# interceptor.net
KiCad netlist of a schematic drawn in EAGLE
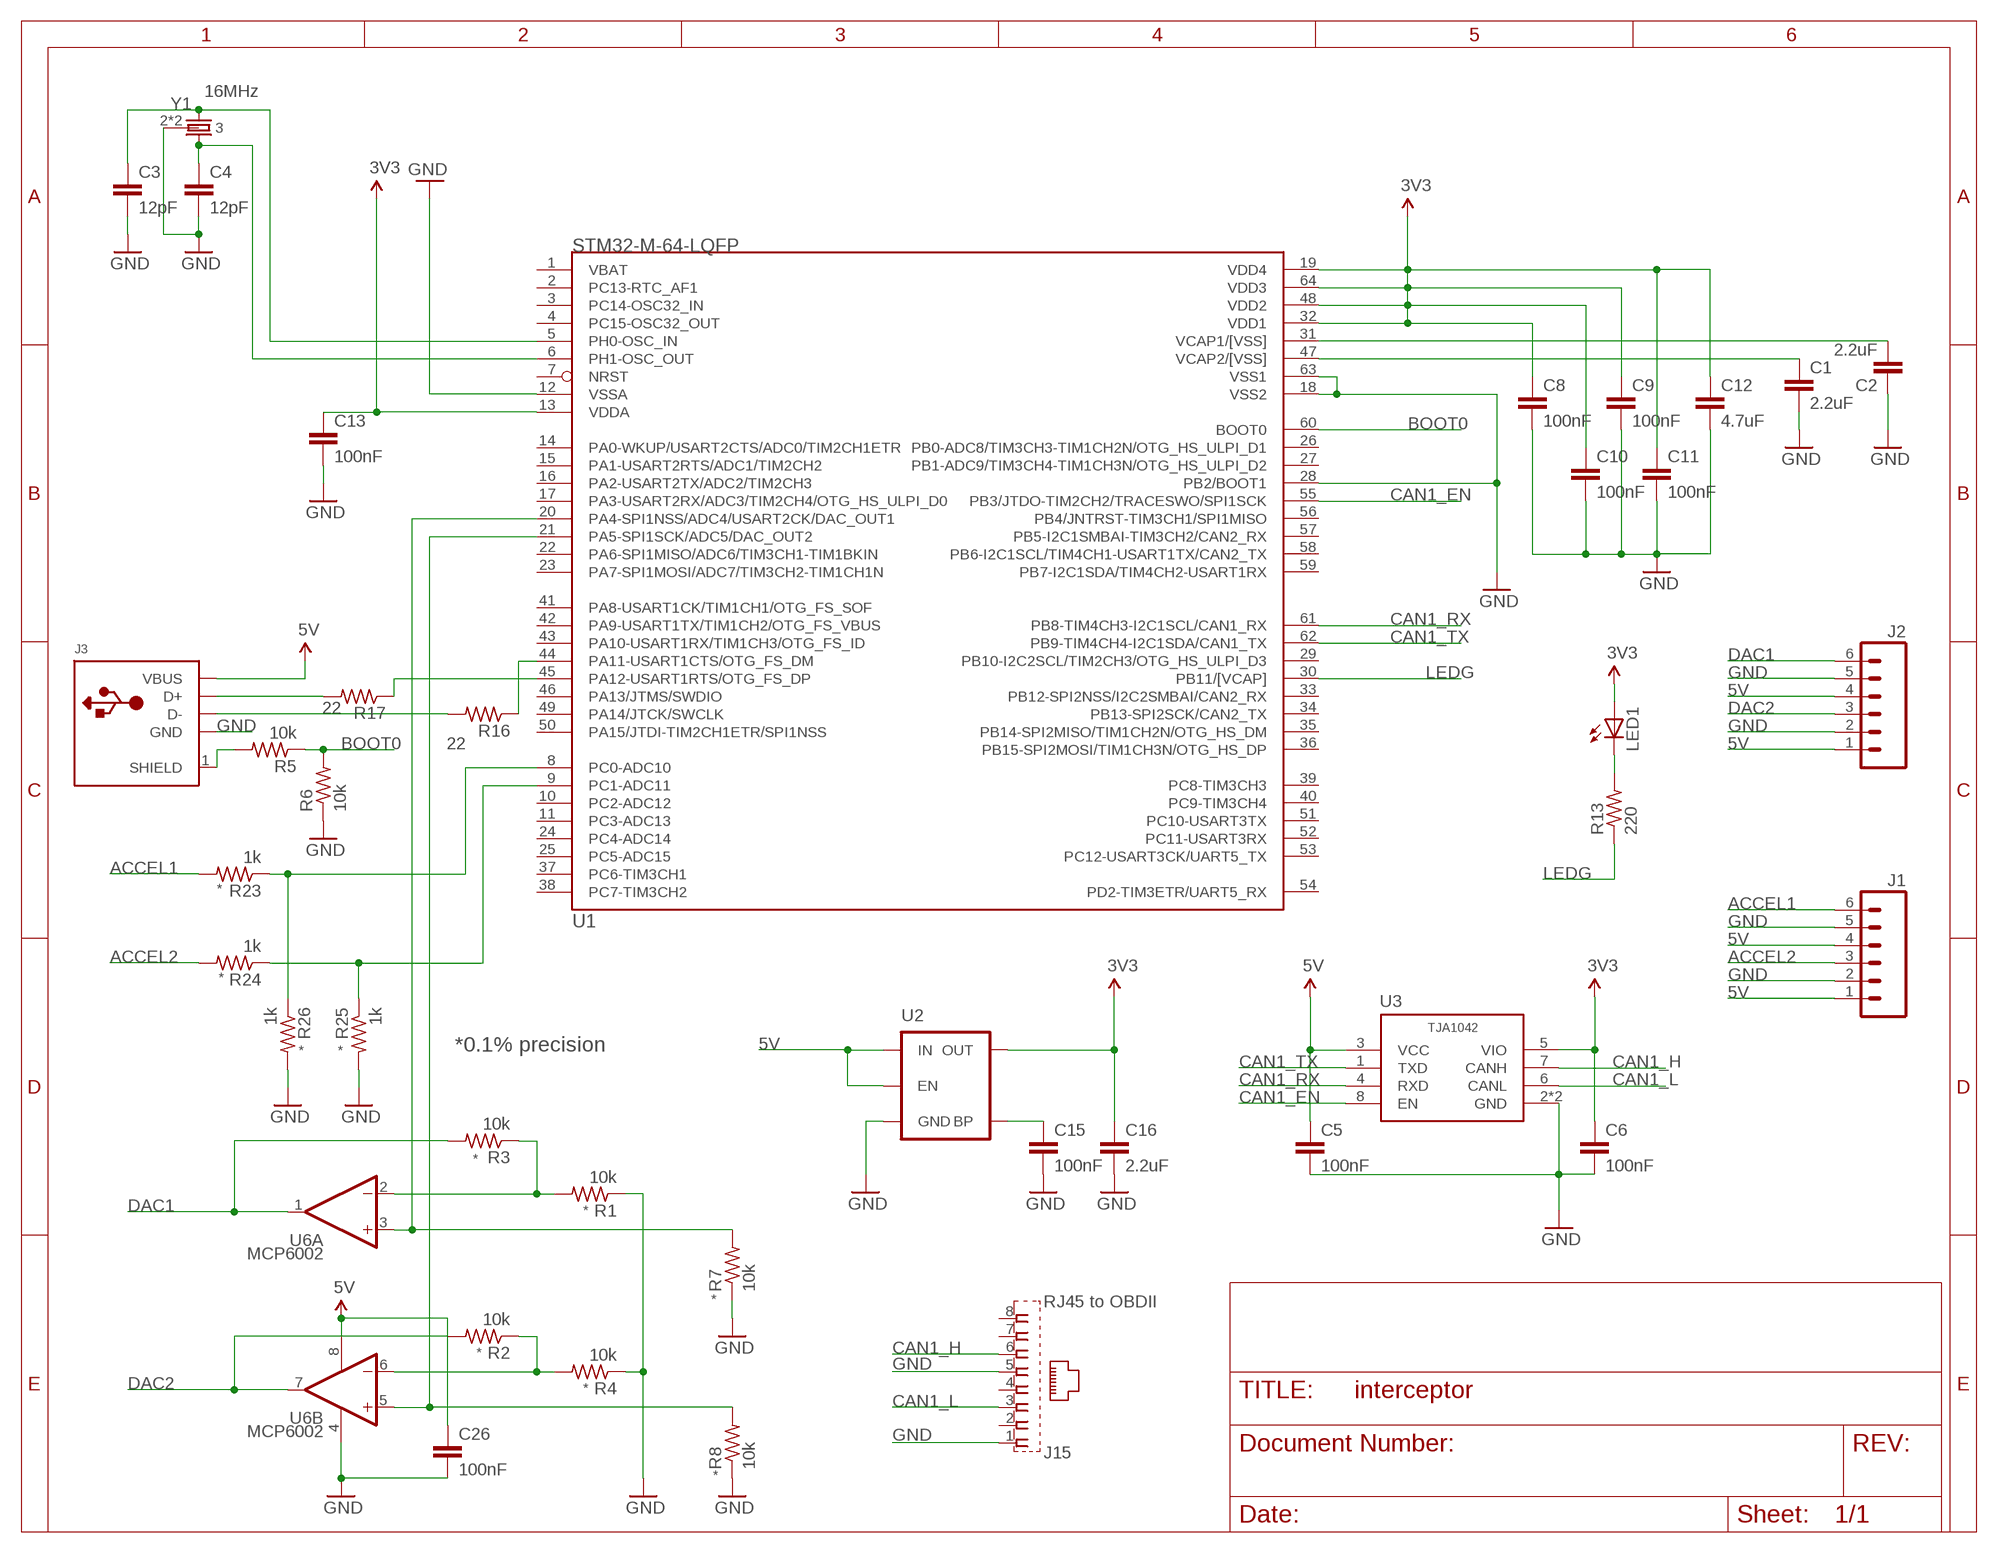
[diagram p0: schematic, sheet 1]

(export (version "E")
  (design (tool "Eeschema 10.0.6"))
  (components
    (comp (ref "C1")
      (value "2.2uF")
      (footprint "eagle-import:0603-C")
      (libsource (lib "eagle-import") (part "C0603"))
    )
    (comp (ref "C2")
      (value "2.2uF")
      (footprint "eagle-import:0603-C")
      (libsource (lib "eagle-import") (part "C0603"))
    )
    (comp (ref "C3")
      (value "12pF")
      (footprint "eagle-import:0603-C")
      (libsource (lib "eagle-import") (part "C0603"))
    )
    (comp (ref "C4")
      (value "12pF")
      (footprint "eagle-import:0603-C")
      (libsource (lib "eagle-import") (part "C0603"))
    )
    (comp (ref "C5")
      (value "100nF")
      (footprint "eagle-import:0603-C")
      (libsource (lib "eagle-import") (part "C0603"))
    )
    (comp (ref "C6")
      (value "100nF")
      (footprint "eagle-import:0603-C")
      (libsource (lib "eagle-import") (part "C0603"))
    )
    (comp (ref "C8")
      (value "100nF")
      (footprint "eagle-import:0603-C")
      (libsource (lib "eagle-import") (part "C0603"))
    )
    (comp (ref "C9")
      (value "100nF")
      (footprint "eagle-import:0603-C")
      (libsource (lib "eagle-import") (part "C0603"))
    )
    (comp (ref "C10")
      (value "100nF")
      (footprint "eagle-import:0603-C")
      (libsource (lib "eagle-import") (part "C0603"))
    )
    (comp (ref "C11")
      (value "100nF")
      (footprint "eagle-import:0603-C")
      (libsource (lib "eagle-import") (part "C0603"))
    )
    (comp (ref "C12")
      (value "4.7uF")
      (footprint "eagle-import:0603-C")
      (libsource (lib "eagle-import") (part "C0603"))
    )
    (comp (ref "C13")
      (value "100nF")
      (footprint "eagle-import:0603-C")
      (libsource (lib "eagle-import") (part "C0603"))
    )
    (comp (ref "C15")
      (value "100nF")
      (footprint "eagle-import:0603-C")
      (libsource (lib "eagle-import") (part "C0603"))
    )
    (comp (ref "C16")
      (value "2.2uF")
      (footprint "eagle-import:0603-C")
      (libsource (lib "eagle-import") (part "C0603"))
    )
    (comp (ref "C26")
      (value "100nF")
      (footprint "eagle-import:0603-C")
      (libsource (lib "eagle-import") (part "C0603"))
    )
    (comp (ref "J1")
      (value "M06NO_SILK_YES_STOP")
      (footprint "eagle-import:1X06_NO_SILK_YES_STOP")
      (libsource (lib "eagle-import") (part "M06NO_SILK_YES_STOP"))
    )
    (comp (ref "J2")
      (value "M06NO_SILK_YES_STOP")
      (footprint "eagle-import:1X06_NO_SILK_YES_STOP")
      (libsource (lib "eagle-import") (part "M06NO_SILK_YES_STOP"))
    )
    (comp (ref "J3")
      (value "USB-ASMD-F")
      (footprint "eagle-import:USB-A-S")
      (libsource (lib "eagle-import") (part "USB-ASMD-F"))
    )
    (comp (ref "J15")
      (value "RJ45 to OBDII")
      (footprint "eagle-import:RA-RJ45")
      (libsource (lib "eagle-import") (part "RA-RJ45RA"))
    )
    (comp (ref "LED1")
      (value "LEDCHIPLED_0805")
      (footprint "eagle-import:CHIPLED_0805")
      (libsource (lib "eagle-import") (part "LEDCHIPLED_0805"))
    )
    (comp (ref "R1")
      (value "10k")
      (footprint "eagle-import:0402-R")
      (libsource (lib "eagle-import") (part "R0402"))
    )
    (comp (ref "R2")
      (value "10k")
      (footprint "eagle-import:0402-R")
      (libsource (lib "eagle-import") (part "R0402"))
    )
    (comp (ref "R3")
      (value "10k")
      (footprint "eagle-import:0402-R")
      (libsource (lib "eagle-import") (part "R0402"))
    )
    (comp (ref "R4")
      (value "10k")
      (footprint "eagle-import:0402-R")
      (libsource (lib "eagle-import") (part "R0402"))
    )
    (comp (ref "R5")
      (value "10k")
      (footprint "eagle-import:0402-R")
      (libsource (lib "eagle-import") (part "R0402"))
    )
    (comp (ref "R6")
      (value "10k")
      (footprint "eagle-import:0402-R")
      (libsource (lib "eagle-import") (part "R0402"))
    )
    (comp (ref "R7")
      (value "10k")
      (footprint "eagle-import:0402-R")
      (libsource (lib "eagle-import") (part "R0402"))
    )
    (comp (ref "R8")
      (value "10k")
      (footprint "eagle-import:0402-R")
      (libsource (lib "eagle-import") (part "R0402"))
    )
    (comp (ref "R13")
      (value "220")
      (footprint "eagle-import:0402-R")
      (libsource (lib "eagle-import") (part "R0402"))
    )
    (comp (ref "R16")
      (value "22")
      (footprint "eagle-import:0402-R")
      (libsource (lib "eagle-import") (part "R0402"))
    )
    (comp (ref "R17")
      (value "22")
      (footprint "eagle-import:0402-R")
      (libsource (lib "eagle-import") (part "R0402"))
    )
    (comp (ref "R23")
      (value "1k")
      (footprint "eagle-import:0402-R")
      (libsource (lib "eagle-import") (part "R0402"))
    )
    (comp (ref "R24")
      (value "1k")
      (footprint "eagle-import:0402-R")
      (libsource (lib "eagle-import") (part "R0402"))
    )
    (comp (ref "R25")
      (value "1k")
      (footprint "eagle-import:0402-R")
      (libsource (lib "eagle-import") (part "R0402"))
    )
    (comp (ref "R26")
      (value "1k")
      (footprint "eagle-import:0402-R")
      (libsource (lib "eagle-import") (part "R0402"))
    )
    (comp (ref "U1")
      (value "STM32-M-64-LQFP")
      (footprint "eagle-import:LQFP64")
      (libsource (lib "eagle-import") (part "STM32-M-64-LQFP"))
    )
    (comp (ref "U2")
      (value "MIC52053.3V")
      (footprint "eagle-import:SOT23-5")
      (libsource (lib "eagle-import") (part "MIC52053.3V"))
    )
    (comp (ref "U3")
      (value "TJA1042HVSON")
      (footprint "eagle-import:HVSON8")
      (libsource (lib "eagle-import") (part "TJA1042HVSON"))
    )
    (comp (ref "U6")
      (value "MCP6002")
      (footprint "eagle-import:SO08")
      (libsource (lib "eagle-import") (part "LM358D"))
    )
    (comp (ref "Y1")
      (value "16MHz")
      (footprint "eagle-import:XTAL-3.2X2.5")
      (libsource (lib "eagle-import") (part "CRYSTAL-3.2X2.54-PIN"))
    )
  )
  (nets
    (net (code "1") (name "/ACCEL1") (class "Default")
      (node (ref "J1") (pin "6") (pinfunction "6_6") (pintype "passive"))
      (node (ref "R23") (pin "2") (pinfunction "2_2") (pintype "passive"))
    )
    (net (code "2") (name "/ACCEL2") (class "Default")
      (node (ref "J1") (pin "3") (pinfunction "3_3") (pintype "passive"))
      (node (ref "R24") (pin "2") (pinfunction "2_2") (pintype "passive"))
    )
    (net (code "3") (name "/BOOT0") (class "Default")
      (node (ref "R5") (pin "1") (pinfunction "1_1") (pintype "passive"))
      (node (ref "R6") (pin "2") (pinfunction "2_2") (pintype "passive"))
      (node (ref "U1") (pin "60") (pinfunction "BOOT0_60") (pintype "input"))
    )
    (net (code "4") (name "/CAN1_EN") (class "Default")
      (node (ref "U1") (pin "55") (pinfunction "PB3/JTDO-TIM2CH2/TRACESWO/SPI1SCK_55") (pintype "bidirectional"))
      (node (ref "U3") (pin "8") (pinfunction "EN_8") (pintype "bidirectional"))
    )
    (net (code "5") (name "/CAN1_H") (class "Default")
      (node (ref "J15") (pin "6") (pinfunction "6_6") (pintype "passive"))
      (node (ref "U3") (pin "7") (pinfunction "CANH_7") (pintype "bidirectional"))
    )
    (net (code "6") (name "/CAN1_L") (class "Default")
      (node (ref "J15") (pin "3") (pinfunction "3_3") (pintype "passive"))
      (node (ref "U3") (pin "6") (pinfunction "CANL_6") (pintype "bidirectional"))
    )
    (net (code "7") (name "/CAN1_RX") (class "Default")
      (node (ref "U1") (pin "61") (pinfunction "PB8-TIM4CH3-I2C1SCL/CAN1_RX_61") (pintype "bidirectional"))
      (node (ref "U3") (pin "4") (pinfunction "RXD_4") (pintype "bidirectional"))
    )
    (net (code "8") (name "/CAN1_TX") (class "Default")
      (node (ref "U1") (pin "62") (pinfunction "PB9-TIM4CH4-I2C1SDA/CAN1_TX_62") (pintype "bidirectional"))
      (node (ref "U3") (pin "1") (pinfunction "TXD_1") (pintype "bidirectional"))
    )
    (net (code "9") (name "/DAC1") (class "Default")
      (node (ref "J2") (pin "6") (pinfunction "6_6") (pintype "passive"))
      (node (ref "R3") (pin "2") (pinfunction "2_2") (pintype "passive"))
      (node (ref "U6") (pin "1") (pinfunction "OUT_1") (pintype "output"))
    )
    (net (code "10") (name "/DAC2") (class "Default")
      (node (ref "J2") (pin "3") (pinfunction "3_3") (pintype "passive"))
      (node (ref "R2") (pin "2") (pinfunction "2_2") (pintype "passive"))
      (node (ref "U6") (pin "7") (pinfunction "OUT_7") (pintype "output"))
    )
    (net (code "11") (name "/LEDG") (class "Default")
      (node (ref "R13") (pin "1") (pinfunction "1_1") (pintype "passive"))
      (node (ref "U1") (pin "30") (pinfunction "PB11/[VCAP]_30") (pintype "bidirectional"))
    )
    (net (code "12") (name "/VBAT") (class "Default")
      (node (ref "U1") (pin "1") (pinfunction "VBAT_1") (pintype "power_in"))
    )
    (net (code "13") (name "3V3") (class "Default")
      (node (ref "C10") (pin "1") (pinfunction "1_1") (pintype "passive"))
      (node (ref "C11") (pin "1") (pinfunction "1_1") (pintype "passive"))
      (node (ref "C12") (pin "1") (pinfunction "1_1") (pintype "passive"))
      (node (ref "C13") (pin "1") (pinfunction "1_1") (pintype "passive"))
      (node (ref "C16") (pin "1") (pinfunction "1_1") (pintype "passive"))
      (node (ref "C6") (pin "1") (pinfunction "1_1") (pintype "passive"))
      (node (ref "C8") (pin "1") (pinfunction "1_1") (pintype "passive"))
      (node (ref "C9") (pin "1") (pinfunction "1_1") (pintype "passive"))
      (node (ref "LED1") (pin "A") (pinfunction "A_A") (pintype "passive"))
      (node (ref "U1") (pin "13") (pinfunction "VDDA_13") (pintype "power_in"))
      (node (ref "U1") (pin "19") (pinfunction "VDD4_19") (pintype "bidirectional"))
      (node (ref "U1") (pin "32") (pinfunction "VDD1_32") (pintype "power_in"))
      (node (ref "U1") (pin "48") (pinfunction "VDD2_48") (pintype "power_in"))
      (node (ref "U1") (pin "64") (pinfunction "VDD3_64") (pintype "power_in"))
      (node (ref "U2") (pin "5") (pinfunction "OUT_5") (pintype "passive"))
      (node (ref "U3") (pin "5") (pinfunction "VIO_5") (pintype "bidirectional"))
    )
    (net (code "14") (name "5V") (class "Default")
      (node (ref "C26") (pin "1") (pinfunction "1_1") (pintype "passive"))
      (node (ref "C5") (pin "1") (pinfunction "1_1") (pintype "passive"))
      (node (ref "J1") (pin "1") (pinfunction "1_1") (pintype "passive"))
      (node (ref "J1") (pin "4") (pinfunction "4_4") (pintype "passive"))
      (node (ref "J2") (pin "1") (pinfunction "1_1") (pintype "passive"))
      (node (ref "J2") (pin "4") (pinfunction "4_4") (pintype "passive"))
      (node (ref "J3") (pin "VBUS") (pinfunction "VBUS_VBUS") (pintype "power_in"))
      (node (ref "U2") (pin "1") (pinfunction "IN_1") (pintype "input"))
      (node (ref "U2") (pin "3") (pinfunction "EN_3") (pintype "input"))
      (node (ref "U3") (pin "3") (pinfunction "VCC_3") (pintype "bidirectional"))
      (node (ref "U6") (pin "8") (pinfunction "V+_8") (pintype "power_in"))
    )
    (net (code "15") (name "GND") (class "Default")
      (node (ref "C1") (pin "2") (pinfunction "2_2") (pintype "passive"))
      (node (ref "C10") (pin "2") (pinfunction "2_2") (pintype "passive"))
      (node (ref "C11") (pin "2") (pinfunction "2_2") (pintype "passive"))
      (node (ref "C12") (pin "2") (pinfunction "2_2") (pintype "passive"))
      (node (ref "C13") (pin "2") (pinfunction "2_2") (pintype "passive"))
      (node (ref "C15") (pin "2") (pinfunction "2_2") (pintype "passive"))
      (node (ref "C16") (pin "2") (pinfunction "2_2") (pintype "passive"))
      (node (ref "C2") (pin "1") (pinfunction "1_1") (pintype "passive"))
      (node (ref "C26") (pin "2") (pinfunction "2_2") (pintype "passive"))
      (node (ref "C3") (pin "2") (pinfunction "2_2") (pintype "passive"))
      (node (ref "C4") (pin "2") (pinfunction "2_2") (pintype "passive"))
      (node (ref "C5") (pin "2") (pinfunction "2_2") (pintype "passive"))
      (node (ref "C6") (pin "2") (pinfunction "2_2") (pintype "passive"))
      (node (ref "C8") (pin "2") (pinfunction "2_2") (pintype "passive"))
      (node (ref "C9") (pin "2") (pinfunction "2_2") (pintype "passive"))
      (node (ref "J1") (pin "2") (pinfunction "2_2") (pintype "passive"))
      (node (ref "J1") (pin "5") (pinfunction "5_5") (pintype "passive"))
      (node (ref "J15") (pin "1") (pinfunction "1_1") (pintype "passive"))
      (node (ref "J15") (pin "5") (pinfunction "5_5") (pintype "passive"))
      (node (ref "J2") (pin "2") (pinfunction "2_2") (pintype "passive"))
      (node (ref "J2") (pin "5") (pinfunction "5_5") (pintype "passive"))
      (node (ref "J3") (pin "GND") (pinfunction "GND_GND") (pintype "power_in"))
      (node (ref "R1") (pin "1") (pinfunction "1_1") (pintype "passive"))
      (node (ref "R25") (pin "2") (pinfunction "2_2") (pintype "passive"))
      (node (ref "R26") (pin "2") (pinfunction "2_2") (pintype "passive"))
      (node (ref "R4") (pin "1") (pinfunction "1_1") (pintype "passive"))
      (node (ref "R6") (pin "1") (pinfunction "1_1") (pintype "passive"))
      (node (ref "R7") (pin "1") (pinfunction "1_1") (pintype "passive"))
      (node (ref "R8") (pin "1") (pinfunction "1_1") (pintype "passive"))
      (node (ref "U1") (pin "12") (pinfunction "VSSA_12") (pintype "power_in"))
      (node (ref "U1") (pin "18") (pinfunction "VSS2_18") (pintype "bidirectional"))
      (node (ref "U1") (pin "28") (pinfunction "PB2/BOOT1_28") (pintype "bidirectional"))
      (node (ref "U1") (pin "63") (pinfunction "VSS1_63") (pintype "power_in"))
      (node (ref "U2") (pin "2") (pinfunction "GND_2") (pintype "input"))
      (node (ref "U3") (pin "2") (pinfunction "GND_2") (pintype "bidirectional"))
      (node (ref "U3") (pin "PAD") (pinfunction "GND_PAD") (pintype "bidirectional"))
      (node (ref "U6") (pin "4") (pinfunction "V-_4") (pintype "power_in"))
      (node (ref "Y1") (pin "2") (pinfunction "3_2") (pintype "bidirectional"))
      (node (ref "Y1") (pin "4") (pinfunction "3_4") (pintype "bidirectional"))
    )
    (net (code "16") (name "Net-(J3-PadD+)") (class "Default")
      (node (ref "J3") (pin "D+") (pinfunction "D+_D+") (pintype "bidirectional"))
      (node (ref "R17") (pin "2") (pinfunction "2_2") (pintype "passive"))
    )
    (net (code "17") (name "Net-(J3-PadD-)") (class "Default")
      (node (ref "J3") (pin "D-") (pinfunction "D-_D-") (pintype "bidirectional"))
      (node (ref "R16") (pin "2") (pinfunction "2_2") (pintype "passive"))
    )
    (net (code "18") (name "Net-(J3-SHIELD)") (class "Default")
      (node (ref "J3") (pin "1") (pinfunction "SHIELD_1") (pintype "bidirectional"))
      (node (ref "R5") (pin "2") (pinfunction "2_2") (pintype "passive"))
    )
    (net (code "19") (name "Net-(LED1-PadC)") (class "Default")
      (node (ref "LED1") (pin "C") (pinfunction "C_C") (pintype "passive"))
      (node (ref "R13") (pin "2") (pinfunction "2_2") (pintype "passive"))
    )
    (net (code "20") (name "Net-(U1-PA4-SPI1NSS{slash}ADC4{slash}USART2CK{slash}DAC_OUT1)") (class "Default")
      (node (ref "R7") (pin "2") (pinfunction "2_2") (pintype "passive"))
      (node (ref "U1") (pin "20") (pinfunction "PA4-SPI1NSS/ADC4/USART2CK/DAC_OUT1_20") (pintype "bidirectional"))
      (node (ref "U6") (pin "3") (pinfunction "+IN_3") (pintype "input"))
    )
    (net (code "21") (name "Net-(U1-PA5-SPI1SCK{slash}ADC5{slash}DAC_OUT2)") (class "Default")
      (node (ref "R8") (pin "2") (pinfunction "2_2") (pintype "passive"))
      (node (ref "U1") (pin "21") (pinfunction "PA5-SPI1SCK/ADC5/DAC_OUT2_21") (pintype "bidirectional"))
      (node (ref "U6") (pin "5") (pinfunction "+IN_5") (pintype "input"))
    )
    (net (code "22") (name "Net-(U1-PA11-USART1CTS{slash}OTG_FS_DM)") (class "Default")
      (node (ref "R16") (pin "1") (pinfunction "1_1") (pintype "passive"))
      (node (ref "U1") (pin "44") (pinfunction "PA11-USART1CTS/OTG_FS_DM_44") (pintype "bidirectional"))
    )
    (net (code "23") (name "Net-(U1-PA12-USART1RTS{slash}OTG_FS_DP)") (class "Default")
      (node (ref "R17") (pin "1") (pinfunction "1_1") (pintype "passive"))
      (node (ref "U1") (pin "45") (pinfunction "PA12-USART1RTS/OTG_FS_DP_45") (pintype "bidirectional"))
    )
    (net (code "24") (name "Net-(U1-PC0-ADC10)") (class "Default")
      (node (ref "R23") (pin "1") (pinfunction "1_1") (pintype "passive"))
      (node (ref "R26") (pin "1") (pinfunction "1_1") (pintype "passive"))
      (node (ref "U1") (pin "8") (pinfunction "PC0-ADC10_8") (pintype "bidirectional"))
    )
    (net (code "25") (name "Net-(U1-PC1-ADC11)") (class "Default")
      (node (ref "R24") (pin "1") (pinfunction "1_1") (pintype "passive"))
      (node (ref "R25") (pin "1") (pinfunction "1_1") (pintype "passive"))
      (node (ref "U1") (pin "9") (pinfunction "PC1-ADC11_9") (pintype "bidirectional"))
    )
    (net (code "26") (name "Net-(U1-PH0-OSC_IN)") (class "Default")
      (node (ref "C3") (pin "1") (pinfunction "1_1") (pintype "passive"))
      (node (ref "U1") (pin "5") (pinfunction "PH0-OSC_IN_5") (pintype "input"))
      (node (ref "Y1") (pin "1") (pinfunction "1_1") (pintype "passive"))
    )
    (net (code "27") (name "Net-(U1-PH1-OSC_OUT)") (class "Default")
      (node (ref "C4") (pin "1") (pinfunction "1_1") (pintype "passive"))
      (node (ref "U1") (pin "6") (pinfunction "PH1-OSC_OUT_6") (pintype "output"))
      (node (ref "Y1") (pin "3") (pinfunction "2_3") (pintype "passive"))
    )
    (net (code "28") (name "Net-(U1-VCAP1{slash}[VSS])") (class "Default")
      (node (ref "C2") (pin "2") (pinfunction "2_2") (pintype "passive"))
      (node (ref "U1") (pin "31") (pinfunction "VCAP1/[VSS]_31") (pintype "power_in"))
    )
    (net (code "29") (name "Net-(U1-VCAP2{slash}[VSS])") (class "Default")
      (node (ref "C1") (pin "1") (pinfunction "1_1") (pintype "passive"))
      (node (ref "U1") (pin "47") (pinfunction "VCAP2/[VSS]_47") (pintype "power_in"))
    )
    (net (code "30") (name "Net-(U2-BP)") (class "Default")
      (node (ref "C15") (pin "1") (pinfunction "1_1") (pintype "passive"))
      (node (ref "U2") (pin "4") (pinfunction "BP_4") (pintype "input"))
    )
    (net (code "31") (name "Net-(U6A--IN)") (class "Default")
      (node (ref "R1") (pin "2") (pinfunction "2_2") (pintype "passive"))
      (node (ref "R3") (pin "1") (pinfunction "1_1") (pintype "passive"))
      (node (ref "U6") (pin "2") (pinfunction "-IN_2") (pintype "input"))
    )
    (net (code "32") (name "Net-(U6B--IN)") (class "Default")
      (node (ref "R2") (pin "1") (pinfunction "1_1") (pintype "passive"))
      (node (ref "R4") (pin "2") (pinfunction "2_2") (pintype "passive"))
      (node (ref "U6") (pin "6") (pinfunction "-IN_6") (pintype "input"))
    )
    (net (code "33") (name "unconnected-(J15-Pad2)") (class "Default")
      (node (ref "J15") (pin "2") (pinfunction "2_2") (pintype "passive"))
    )
    (net (code "34") (name "unconnected-(J15-Pad4)") (class "Default")
      (node (ref "J15") (pin "4") (pinfunction "4_4") (pintype "passive"))
    )
    (net (code "35") (name "unconnected-(J15-Pad7)") (class "Default")
      (node (ref "J15") (pin "7") (pinfunction "7_7") (pintype "passive"))
    )
    (net (code "36") (name "unconnected-(J15-Pad8)") (class "Default")
      (node (ref "J15") (pin "8") (pinfunction "8_8") (pintype "passive"))
    )
    (net (code "37") (name "unconnected-(U1-NRST-Pad7)") (class "Default")
      (node (ref "U1") (pin "7") (pinfunction "NRST_7") (pintype "bidirectional"))
    )
    (net (code "38") (name "unconnected-(U1-PA0-WKUP{slash}USART2CTS{slash}ADC0{slash}TIM2CH1ETR-Pad14)") (class "Default")
      (node (ref "U1") (pin "14") (pinfunction "PA0-WKUP/USART2CTS/ADC0/TIM2CH1ETR_14") (pintype "bidirectional"))
    )
    (net (code "39") (name "unconnected-(U1-PA1-USART2RTS{slash}ADC1{slash}TIM2CH2-Pad15)") (class "Default")
      (node (ref "U1") (pin "15") (pinfunction "PA1-USART2RTS/ADC1/TIM2CH2_15") (pintype "bidirectional"))
    )
    (net (code "40") (name "unconnected-(U1-PA2-USART2TX{slash}ADC2{slash}TIM2CH3-Pad16)") (class "Default")
      (node (ref "U1") (pin "16") (pinfunction "PA2-USART2TX/ADC2/TIM2CH3_16") (pintype "bidirectional"))
    )
    (net (code "41") (name "unconnected-(U1-PA3-USART2RX{slash}ADC3{slash}TIM2CH4{slash}OTG_HS_ULPI_D0-Pad17)") (class "Default")
      (node (ref "U1") (pin "17") (pinfunction "PA3-USART2RX/ADC3/TIM2CH4/OTG_HS_ULPI_D0_17") (pintype "bidirectional"))
    )
    (net (code "42") (name "unconnected-(U1-PA6-SPI1MISO{slash}ADC6{slash}TIM3CH1-TIM1BKIN-Pad22)") (class "Default")
      (node (ref "U1") (pin "22") (pinfunction "PA6-SPI1MISO/ADC6/TIM3CH1-TIM1BKIN_22") (pintype "bidirectional"))
    )
    (net (code "43") (name "unconnected-(U1-PA7-SPI1MOSI{slash}ADC7{slash}TIM3CH2-TIM1CH1N-Pad23)") (class "Default")
      (node (ref "U1") (pin "23") (pinfunction "PA7-SPI1MOSI/ADC7/TIM3CH2-TIM1CH1N_23") (pintype "bidirectional"))
    )
    (net (code "44") (name "unconnected-(U1-PA8-USART1CK{slash}TIM1CH1{slash}OTG_FS_SOF-Pad41)") (class "Default")
      (node (ref "U1") (pin "41") (pinfunction "PA8-USART1CK/TIM1CH1/OTG_FS_SOF_41") (pintype "bidirectional"))
    )
    (net (code "45") (name "unconnected-(U1-PA9-USART1TX{slash}TIM1CH2{slash}OTG_FS_VBUS-Pad42)") (class "Default")
      (node (ref "U1") (pin "42") (pinfunction "PA9-USART1TX/TIM1CH2/OTG_FS_VBUS_42") (pintype "bidirectional"))
    )
    (net (code "46") (name "unconnected-(U1-PA10-USART1RX{slash}TIM1CH3{slash}OTG_FS_ID-Pad43)") (class "Default")
      (node (ref "U1") (pin "43") (pinfunction "PA10-USART1RX/TIM1CH3/OTG_FS_ID_43") (pintype "bidirectional"))
    )
    (net (code "47") (name "unconnected-(U1-PA13{slash}JTMS{slash}SWDIO-Pad46)") (class "Default")
      (node (ref "U1") (pin "46") (pinfunction "PA13/JTMS/SWDIO_46") (pintype "bidirectional"))
    )
    (net (code "48") (name "unconnected-(U1-PA14{slash}JTCK{slash}SWCLK-Pad49)") (class "Default")
      (node (ref "U1") (pin "49") (pinfunction "PA14/JTCK/SWCLK_49") (pintype "bidirectional"))
    )
    (net (code "49") (name "unconnected-(U1-PA15{slash}JTDI-TIM2CH1ETR{slash}SPI1NSS-Pad50)") (class "Default")
      (node (ref "U1") (pin "50") (pinfunction "PA15/JTDI-TIM2CH1ETR/SPI1NSS_50") (pintype "bidirectional"))
    )
    (net (code "50") (name "unconnected-(U1-PB0-ADC8{slash}TIM3CH3-TIM1CH2N{slash}OTG_HS_ULPI_D1-Pad26)") (class "Default")
      (node (ref "U1") (pin "26") (pinfunction "PB0-ADC8/TIM3CH3-TIM1CH2N/OTG_HS_ULPI_D1_26") (pintype "bidirectional"))
    )
    (net (code "51") (name "unconnected-(U1-PB1-ADC9{slash}TIM3CH4-TIM1CH3N{slash}OTG_HS_ULPI_D2-Pad27)") (class "Default")
      (node (ref "U1") (pin "27") (pinfunction "PB1-ADC9/TIM3CH4-TIM1CH3N/OTG_HS_ULPI_D2_27") (pintype "bidirectional"))
    )
    (net (code "52") (name "unconnected-(U1-PB4{slash}JNTRST-TIM3CH1{slash}SPI1MISO-Pad56)") (class "Default")
      (node (ref "U1") (pin "56") (pinfunction "PB4/JNTRST-TIM3CH1/SPI1MISO_56") (pintype "bidirectional"))
    )
    (net (code "53") (name "unconnected-(U1-PB5-I2C1SMBAI-TIM3CH2{slash}CAN2_RX-Pad57)") (class "Default")
      (node (ref "U1") (pin "57") (pinfunction "PB5-I2C1SMBAI-TIM3CH2/CAN2_RX_57") (pintype "bidirectional"))
    )
    (net (code "54") (name "unconnected-(U1-PB6-I2C1SCL{slash}TIM4CH1-USART1TX{slash}CAN2_TX-Pad58)") (class "Default")
      (node (ref "U1") (pin "58") (pinfunction "PB6-I2C1SCL/TIM4CH1-USART1TX/CAN2_TX_58") (pintype "bidirectional"))
    )
    (net (code "55") (name "unconnected-(U1-PB7-I2C1SDA{slash}TIM4CH2-USART1RX-Pad59)") (class "Default")
      (node (ref "U1") (pin "59") (pinfunction "PB7-I2C1SDA/TIM4CH2-USART1RX_59") (pintype "bidirectional"))
    )
    (net (code "56") (name "unconnected-(U1-PB10-I2C2SCL{slash}TIM2CH3{slash}OTG_HS_ULPI_D3-Pad29)") (class "Default")
      (node (ref "U1") (pin "29") (pinfunction "PB10-I2C2SCL/TIM2CH3/OTG_HS_ULPI_D3_29") (pintype "bidirectional"))
    )
    (net (code "57") (name "unconnected-(U1-PB12-SPI2NSS{slash}I2C2SMBAI{slash}CAN2_RX-Pad33)") (class "Default")
      (node (ref "U1") (pin "33") (pinfunction "PB12-SPI2NSS/I2C2SMBAI/CAN2_RX_33") (pintype "bidirectional"))
    )
    (net (code "58") (name "unconnected-(U1-PB13-SPI2SCK{slash}CAN2_TX-Pad34)") (class "Default")
      (node (ref "U1") (pin "34") (pinfunction "PB13-SPI2SCK/CAN2_TX_34") (pintype "bidirectional"))
    )
    (net (code "59") (name "unconnected-(U1-PB14-SPI2MISO{slash}TIM1CH2N{slash}OTG_HS_DM-Pad35)") (class "Default")
      (node (ref "U1") (pin "35") (pinfunction "PB14-SPI2MISO/TIM1CH2N/OTG_HS_DM_35") (pintype "bidirectional"))
    )
    (net (code "60") (name "unconnected-(U1-PB15-SPI2MOSI{slash}TIM1CH3N{slash}OTG_HS_DP-Pad36)") (class "Default")
      (node (ref "U1") (pin "36") (pinfunction "PB15-SPI2MOSI/TIM1CH3N/OTG_HS_DP_36") (pintype "bidirectional"))
    )
    (net (code "61") (name "unconnected-(U1-PC2-ADC12-Pad10)") (class "Default")
      (node (ref "U1") (pin "10") (pinfunction "PC2-ADC12_10") (pintype "bidirectional"))
    )
    (net (code "62") (name "unconnected-(U1-PC3-ADC13-Pad11)") (class "Default")
      (node (ref "U1") (pin "11") (pinfunction "PC3-ADC13_11") (pintype "bidirectional"))
    )
    (net (code "63") (name "unconnected-(U1-PC4-ADC14-Pad24)") (class "Default")
      (node (ref "U1") (pin "24") (pinfunction "PC4-ADC14_24") (pintype "bidirectional"))
    )
    (net (code "64") (name "unconnected-(U1-PC5-ADC15-Pad25)") (class "Default")
      (node (ref "U1") (pin "25") (pinfunction "PC5-ADC15_25") (pintype "bidirectional"))
    )
    (net (code "65") (name "unconnected-(U1-PC6-TIM3CH1-Pad37)") (class "Default")
      (node (ref "U1") (pin "37") (pinfunction "PC6-TIM3CH1_37") (pintype "bidirectional"))
    )
    (net (code "66") (name "unconnected-(U1-PC7-TIM3CH2-Pad38)") (class "Default")
      (node (ref "U1") (pin "38") (pinfunction "PC7-TIM3CH2_38") (pintype "bidirectional"))
    )
    (net (code "67") (name "unconnected-(U1-PC8-TIM3CH3-Pad39)") (class "Default")
      (node (ref "U1") (pin "39") (pinfunction "PC8-TIM3CH3_39") (pintype "bidirectional"))
    )
    (net (code "68") (name "unconnected-(U1-PC9-TIM3CH4-Pad40)") (class "Default")
      (node (ref "U1") (pin "40") (pinfunction "PC9-TIM3CH4_40") (pintype "bidirectional"))
    )
    (net (code "69") (name "unconnected-(U1-PC10-USART3TX-Pad51)") (class "Default")
      (node (ref "U1") (pin "51") (pinfunction "PC10-USART3TX_51") (pintype "bidirectional"))
    )
    (net (code "70") (name "unconnected-(U1-PC11-USART3RX-Pad52)") (class "Default")
      (node (ref "U1") (pin "52") (pinfunction "PC11-USART3RX_52") (pintype "bidirectional"))
    )
    (net (code "71") (name "unconnected-(U1-PC12-USART3CK{slash}UART5_TX-Pad53)") (class "Default")
      (node (ref "U1") (pin "53") (pinfunction "PC12-USART3CK/UART5_TX_53") (pintype "bidirectional"))
    )
    (net (code "72") (name "unconnected-(U1-PC13-RTC_AF1-Pad2)") (class "Default")
      (node (ref "U1") (pin "2") (pinfunction "PC13-RTC_AF1_2") (pintype "bidirectional"))
    )
    (net (code "73") (name "unconnected-(U1-PC14-OSC32_IN-Pad3)") (class "Default")
      (node (ref "U1") (pin "3") (pinfunction "PC14-OSC32_IN_3") (pintype "bidirectional"))
    )
    (net (code "74") (name "unconnected-(U1-PC15-OSC32_OUT-Pad4)") (class "Default")
      (node (ref "U1") (pin "4") (pinfunction "PC15-OSC32_OUT_4") (pintype "bidirectional"))
    )
    (net (code "75") (name "unconnected-(U1-PD2-TIM3ETR{slash}UART5_RX-Pad54)") (class "Default")
      (node (ref "U1") (pin "54") (pinfunction "PD2-TIM3ETR/UART5_RX_54") (pintype "bidirectional"))
    )
  )
)
